# lsm_2x_daisy.net
KiCad netlist of a schematic drawn in EAGLE
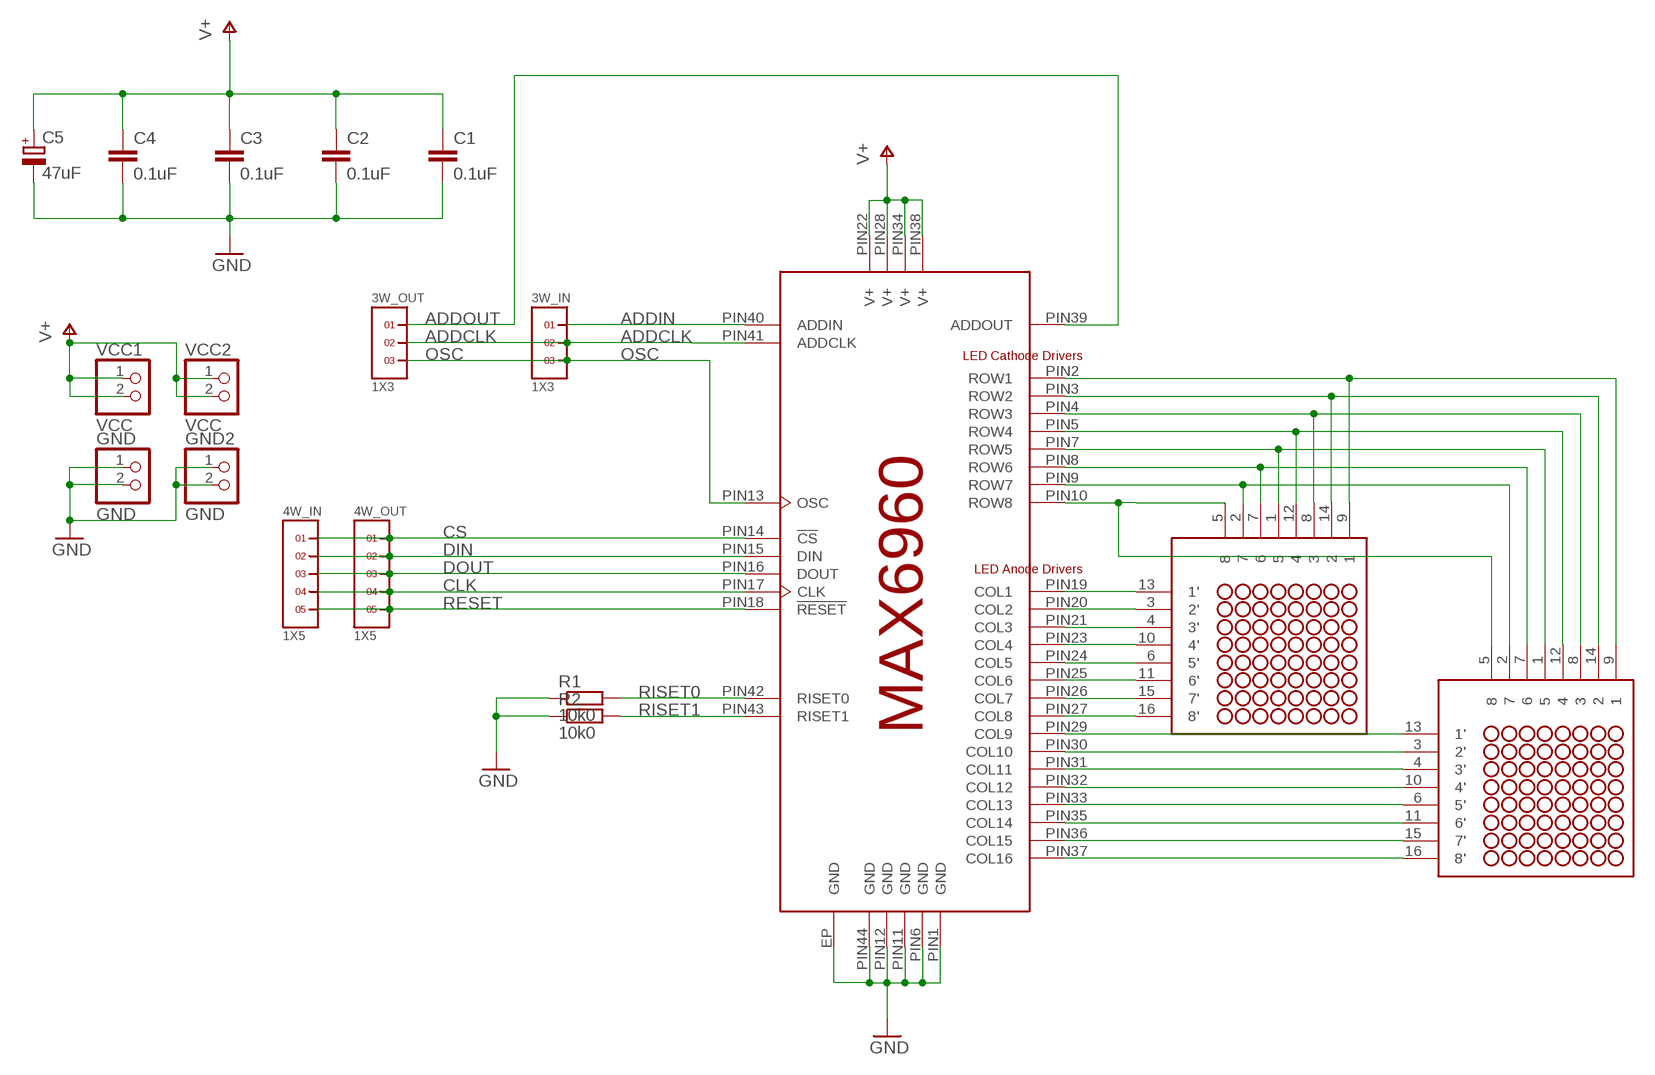
[diagram p0: schematic, sheet 1]

(export (version "E")
  (design (tool "Eeschema 10.0.6"))
  (components
    (comp (ref "3W_IN")
      (value "1X3")
      (footprint "eagle-import:1X3")
      (libsource (lib "eagle-import") (part "1X3"))
    )
    (comp (ref "3W_OUT")
      (value "1X3")
      (footprint "eagle-import:1X3")
      (libsource (lib "eagle-import") (part "1X3"))
    )
    (comp (ref "4W_IN")
      (value "1X5")
      (footprint "eagle-import:1X5")
      (libsource (lib "eagle-import") (part "1X5"))
    )
    (comp (ref "4W_OUT")
      (value "1X5")
      (footprint "eagle-import:1X5")
      (libsource (lib "eagle-import") (part "1X5"))
    )
    (comp (ref "C1")
      (value "0.1uF")
      (footprint "eagle-import:C0805")
      (libsource (lib "eagle-import") (part "C-EUC0805"))
    )
    (comp (ref "C2")
      (value "0.1uF")
      (footprint "eagle-import:C0805")
      (libsource (lib "eagle-import") (part "C-EUC0805"))
    )
    (comp (ref "C3")
      (value "0.1uF")
      (footprint "eagle-import:C0805")
      (libsource (lib "eagle-import") (part "C-EUC0805"))
    )
    (comp (ref "C4")
      (value "0.1uF")
      (footprint "eagle-import:C0805")
      (libsource (lib "eagle-import") (part "C-EUC0805"))
    )
    (comp (ref "C5")
      (value "47uF")
      (footprint "eagle-import:E2-5")
      (libsource (lib "eagle-import") (part "CPOL-EUE2-5"))
    )
    (comp (ref "GND")
      (value "GND")
      (footprint "eagle-import:1X02")
      (libsource (lib "eagle-import") (part "PINHD-1X2"))
    )
    (comp (ref "GND2")
      (value "GND")
      (footprint "eagle-import:1X02")
      (libsource (lib "eagle-import") (part "PINHD-1X2"))
    )
    (comp (ref "M1")
      (value "NFM-12881BG-11LILPADS")
      (footprint "eagle-import:NFM-12881BG-11-SMALL-LILPADS")
      (libsource (lib "eagle-import") (part "NFM-12881BG-11LILPADS"))
    )
    (comp (ref "M2")
      (value "NFM-12881BG-11LILPADS")
      (footprint "eagle-import:NFM-12881BG-11-SMALL-LILPADS")
      (libsource (lib "eagle-import") (part "NFM-12881BG-11LILPADS"))
    )
    (comp (ref "MAX6960")
      (value "MAX6960")
      (footprint "eagle-import:44TQFN-EP")
      (libsource (lib "eagle-import") (part "MAX6960"))
    )
    (comp (ref "R1")
      (value "10k0")
      (footprint "eagle-import:R0805")
      (libsource (lib "eagle-import") (part "R-EU_R0805"))
    )
    (comp (ref "R2")
      (value "10k0")
      (footprint "eagle-import:R0805")
      (libsource (lib "eagle-import") (part "R-EU_R0805"))
    )
    (comp (ref "VCC1")
      (value "VCC")
      (footprint "eagle-import:1X02")
      (libsource (lib "eagle-import") (part "PINHD-1X2"))
    )
    (comp (ref "VCC2")
      (value "VCC")
      (footprint "eagle-import:1X02")
      (libsource (lib "eagle-import") (part "PINHD-1X2"))
    )
  )
  (nets
    (net (code "1") (name "/ADDCLK") (class "Default")
      (node (ref "3W_IN") (pin "2") (pinfunction "2_2") (pintype "bidirectional"))
      (node (ref "3W_OUT") (pin "2") (pinfunction "2_2") (pintype "bidirectional"))
      (node (ref "MAX6960") (pin "PIN41") (pinfunction "ADDCLK_PIN41") (pintype "bidirectional"))
    )
    (net (code "2") (name "/ADDIN") (class "Default")
      (node (ref "3W_IN") (pin "1") (pinfunction "1_1") (pintype "bidirectional"))
      (node (ref "MAX6960") (pin "PIN40") (pinfunction "ADDIN_PIN40") (pintype "input"))
    )
    (net (code "3") (name "/ADDOUT") (class "Default")
      (node (ref "3W_OUT") (pin "1") (pinfunction "1_1") (pintype "bidirectional"))
      (node (ref "MAX6960") (pin "PIN39") (pinfunction "ADDOUT_PIN39") (pintype "output"))
    )
    (net (code "4") (name "/CLK") (class "Default")
      (node (ref "4W_IN") (pin "4") (pinfunction "4_4") (pintype "bidirectional"))
      (node (ref "4W_OUT") (pin "4") (pinfunction "4_4") (pintype "bidirectional"))
      (node (ref "MAX6960") (pin "PIN17") (pinfunction "CLK_PIN17") (pintype "input"))
    )
    (net (code "5") (name "/CS") (class "Default")
      (node (ref "4W_IN") (pin "1") (pinfunction "1_1") (pintype "bidirectional"))
      (node (ref "4W_OUT") (pin "1") (pinfunction "1_1") (pintype "bidirectional"))
      (node (ref "MAX6960") (pin "PIN14") (pinfunction "~{CS}_PIN14") (pintype "input"))
    )
    (net (code "6") (name "/DIN") (class "Default")
      (node (ref "4W_IN") (pin "2") (pinfunction "2_2") (pintype "bidirectional"))
      (node (ref "4W_OUT") (pin "2") (pinfunction "2_2") (pintype "bidirectional"))
      (node (ref "MAX6960") (pin "PIN15") (pinfunction "DIN_PIN15") (pintype "input"))
    )
    (net (code "7") (name "/DOUT") (class "Default")
      (node (ref "4W_IN") (pin "3") (pinfunction "3_3") (pintype "bidirectional"))
      (node (ref "4W_OUT") (pin "3") (pinfunction "3_3") (pintype "bidirectional"))
      (node (ref "MAX6960") (pin "PIN16") (pinfunction "DOUT_PIN16") (pintype "output"))
    )
    (net (code "8") (name "/OSC") (class "Default")
      (node (ref "3W_IN") (pin "3") (pinfunction "3_3") (pintype "bidirectional"))
      (node (ref "3W_OUT") (pin "3") (pinfunction "3_3") (pintype "bidirectional"))
      (node (ref "MAX6960") (pin "PIN13") (pinfunction "OSC_PIN13") (pintype "input"))
    )
    (net (code "9") (name "/RESET") (class "Default")
      (node (ref "4W_IN") (pin "5") (pinfunction "5_5") (pintype "bidirectional"))
      (node (ref "4W_OUT") (pin "5") (pinfunction "5_5") (pintype "bidirectional"))
      (node (ref "MAX6960") (pin "PIN18") (pinfunction "~{RESET}_PIN18") (pintype "input"))
    )
    (net (code "10") (name "/RISET0") (class "Default")
      (node (ref "MAX6960") (pin "PIN42") (pinfunction "RISET0_PIN42") (pintype "input"))
      (node (ref "R1") (pin "2") (pinfunction "2_2") (pintype "passive"))
    )
    (net (code "11") (name "/RISET1") (class "Default")
      (node (ref "MAX6960") (pin "PIN43") (pinfunction "RISET1_PIN43") (pintype "input"))
      (node (ref "R2") (pin "2") (pinfunction "2_2") (pintype "passive"))
    )
    (net (code "12") (name "GND") (class "Default")
      (node (ref "C1") (pin "2") (pinfunction "2_2") (pintype "passive"))
      (node (ref "C2") (pin "2") (pinfunction "2_2") (pintype "passive"))
      (node (ref "C3") (pin "2") (pinfunction "2_2") (pintype "passive"))
      (node (ref "C4") (pin "2") (pinfunction "2_2") (pintype "passive"))
      (node (ref "C5") (pin "-") (pinfunction "-_-") (pintype "passive"))
      (node (ref "GND") (pin "1") (pinfunction "1_1") (pintype "passive"))
      (node (ref "GND") (pin "2") (pinfunction "2_2") (pintype "passive"))
      (node (ref "GND2") (pin "1") (pinfunction "1_1") (pintype "passive"))
      (node (ref "GND2") (pin "2") (pinfunction "2_2") (pintype "passive"))
      (node (ref "MAX6960") (pin "EP") (pinfunction "GND_EP") (pintype "power_in"))
      (node (ref "MAX6960") (pin "PIN1") (pinfunction "GND_PIN1") (pintype "power_in"))
      (node (ref "MAX6960") (pin "PIN11") (pinfunction "GND_PIN11") (pintype "power_in"))
      (node (ref "MAX6960") (pin "PIN12") (pinfunction "GND_PIN12") (pintype "power_in"))
      (node (ref "MAX6960") (pin "PIN44") (pinfunction "GND_PIN44") (pintype "power_in"))
      (node (ref "MAX6960") (pin "PIN6") (pinfunction "GND_PIN6") (pintype "power_in"))
      (node (ref "R1") (pin "1") (pinfunction "1_1") (pintype "passive"))
      (node (ref "R2") (pin "1") (pinfunction "1_1") (pintype "passive"))
    )
    (net (code "13") (name "Net-(M1-1')") (class "Default")
      (node (ref "M1") (pin "13") (pinfunction "1'_13") (pintype "bidirectional"))
      (node (ref "MAX6960") (pin "PIN19") (pinfunction "COL1_PIN19") (pintype "output"))
    )
    (net (code "14") (name "Net-(M1-1)") (class "Default")
      (node (ref "M1") (pin "9") (pinfunction "1_9") (pintype "input"))
      (node (ref "M2") (pin "9") (pinfunction "1_9") (pintype "input"))
      (node (ref "MAX6960") (pin "PIN2") (pinfunction "ROW1_PIN2") (pintype "output"))
    )
    (net (code "15") (name "Net-(M1-2')") (class "Default")
      (node (ref "M1") (pin "3") (pinfunction "2'_3") (pintype "bidirectional"))
      (node (ref "MAX6960") (pin "PIN20") (pinfunction "COL2_PIN20") (pintype "output"))
    )
    (net (code "16") (name "Net-(M1-2)") (class "Default")
      (node (ref "M1") (pin "14") (pinfunction "2_14") (pintype "input"))
      (node (ref "M2") (pin "14") (pinfunction "2_14") (pintype "input"))
      (node (ref "MAX6960") (pin "PIN3") (pinfunction "ROW2_PIN3") (pintype "output"))
    )
    (net (code "17") (name "Net-(M1-3')") (class "Default")
      (node (ref "M1") (pin "4") (pinfunction "3'_4") (pintype "bidirectional"))
      (node (ref "MAX6960") (pin "PIN21") (pinfunction "COL3_PIN21") (pintype "output"))
    )
    (net (code "18") (name "Net-(M1-3)") (class "Default")
      (node (ref "M1") (pin "8") (pinfunction "3_8") (pintype "input"))
      (node (ref "M2") (pin "8") (pinfunction "3_8") (pintype "input"))
      (node (ref "MAX6960") (pin "PIN4") (pinfunction "ROW3_PIN4") (pintype "output"))
    )
    (net (code "19") (name "Net-(M1-4')") (class "Default")
      (node (ref "M1") (pin "10") (pinfunction "4'_10") (pintype "bidirectional"))
      (node (ref "MAX6960") (pin "PIN23") (pinfunction "COL4_PIN23") (pintype "output"))
    )
    (net (code "20") (name "Net-(M1-4)") (class "Default")
      (node (ref "M1") (pin "12") (pinfunction "4_12") (pintype "input"))
      (node (ref "M2") (pin "12") (pinfunction "4_12") (pintype "input"))
      (node (ref "MAX6960") (pin "PIN5") (pinfunction "ROW4_PIN5") (pintype "output"))
    )
    (net (code "21") (name "Net-(M1-5')") (class "Default")
      (node (ref "M1") (pin "6") (pinfunction "5'_6") (pintype "bidirectional"))
      (node (ref "MAX6960") (pin "PIN24") (pinfunction "COL5_PIN24") (pintype "output"))
    )
    (net (code "22") (name "Net-(M1-5)") (class "Default")
      (node (ref "M1") (pin "1") (pinfunction "5_1") (pintype "input"))
      (node (ref "M2") (pin "1") (pinfunction "5_1") (pintype "input"))
      (node (ref "MAX6960") (pin "PIN7") (pinfunction "ROW5_PIN7") (pintype "output"))
    )
    (net (code "23") (name "Net-(M1-6')") (class "Default")
      (node (ref "M1") (pin "11") (pinfunction "6'_11") (pintype "bidirectional"))
      (node (ref "MAX6960") (pin "PIN25") (pinfunction "COL6_PIN25") (pintype "output"))
    )
    (net (code "24") (name "Net-(M1-6)") (class "Default")
      (node (ref "M1") (pin "7") (pinfunction "6_7") (pintype "input"))
      (node (ref "M2") (pin "7") (pinfunction "6_7") (pintype "input"))
      (node (ref "MAX6960") (pin "PIN8") (pinfunction "ROW6_PIN8") (pintype "output"))
    )
    (net (code "25") (name "Net-(M1-7')") (class "Default")
      (node (ref "M1") (pin "15") (pinfunction "7'_15") (pintype "bidirectional"))
      (node (ref "MAX6960") (pin "PIN26") (pinfunction "COL7_PIN26") (pintype "output"))
    )
    (net (code "26") (name "Net-(M1-7)") (class "Default")
      (node (ref "M1") (pin "2") (pinfunction "7_2") (pintype "input"))
      (node (ref "M2") (pin "2") (pinfunction "7_2") (pintype "input"))
      (node (ref "MAX6960") (pin "PIN9") (pinfunction "ROW7_PIN9") (pintype "output"))
    )
    (net (code "27") (name "Net-(M1-8')") (class "Default")
      (node (ref "M1") (pin "16") (pinfunction "8'_16") (pintype "bidirectional"))
      (node (ref "MAX6960") (pin "PIN27") (pinfunction "COL8_PIN27") (pintype "output"))
    )
    (net (code "28") (name "Net-(M1-8)") (class "Default")
      (node (ref "M1") (pin "5") (pinfunction "8_5") (pintype "input"))
      (node (ref "M2") (pin "5") (pinfunction "8_5") (pintype "input"))
      (node (ref "MAX6960") (pin "PIN10") (pinfunction "ROW8_PIN10") (pintype "output"))
    )
    (net (code "29") (name "Net-(M2-1')") (class "Default")
      (node (ref "M2") (pin "13") (pinfunction "1'_13") (pintype "bidirectional"))
      (node (ref "MAX6960") (pin "PIN29") (pinfunction "COL9_PIN29") (pintype "output"))
    )
    (net (code "30") (name "Net-(M2-2')") (class "Default")
      (node (ref "M2") (pin "3") (pinfunction "2'_3") (pintype "bidirectional"))
      (node (ref "MAX6960") (pin "PIN30") (pinfunction "COL10_PIN30") (pintype "output"))
    )
    (net (code "31") (name "Net-(M2-3')") (class "Default")
      (node (ref "M2") (pin "4") (pinfunction "3'_4") (pintype "bidirectional"))
      (node (ref "MAX6960") (pin "PIN31") (pinfunction "COL11_PIN31") (pintype "output"))
    )
    (net (code "32") (name "Net-(M2-4')") (class "Default")
      (node (ref "M2") (pin "10") (pinfunction "4'_10") (pintype "bidirectional"))
      (node (ref "MAX6960") (pin "PIN32") (pinfunction "COL12_PIN32") (pintype "output"))
    )
    (net (code "33") (name "Net-(M2-5')") (class "Default")
      (node (ref "M2") (pin "6") (pinfunction "5'_6") (pintype "bidirectional"))
      (node (ref "MAX6960") (pin "PIN33") (pinfunction "COL13_PIN33") (pintype "output"))
    )
    (net (code "34") (name "Net-(M2-6')") (class "Default")
      (node (ref "M2") (pin "11") (pinfunction "6'_11") (pintype "bidirectional"))
      (node (ref "MAX6960") (pin "PIN35") (pinfunction "COL14_PIN35") (pintype "output"))
    )
    (net (code "35") (name "Net-(M2-7')") (class "Default")
      (node (ref "M2") (pin "15") (pinfunction "7'_15") (pintype "bidirectional"))
      (node (ref "MAX6960") (pin "PIN36") (pinfunction "COL15_PIN36") (pintype "output"))
    )
    (net (code "36") (name "Net-(M2-8')") (class "Default")
      (node (ref "M2") (pin "16") (pinfunction "8'_16") (pintype "bidirectional"))
      (node (ref "MAX6960") (pin "PIN37") (pinfunction "COL16_PIN37") (pintype "output"))
    )
    (net (code "37") (name "V+") (class "Default")
      (node (ref "C1") (pin "1") (pinfunction "1_1") (pintype "passive"))
      (node (ref "C2") (pin "1") (pinfunction "1_1") (pintype "passive"))
      (node (ref "C3") (pin "1") (pinfunction "1_1") (pintype "passive"))
      (node (ref "C4") (pin "1") (pinfunction "1_1") (pintype "passive"))
      (node (ref "C5") (pin "+") (pinfunction "+_+") (pintype "passive"))
      (node (ref "MAX6960") (pin "PIN22") (pinfunction "V+_PIN22") (pintype "power_in"))
      (node (ref "MAX6960") (pin "PIN28") (pinfunction "V+_PIN28") (pintype "power_in"))
      (node (ref "MAX6960") (pin "PIN34") (pinfunction "V+_PIN34") (pintype "power_in"))
      (node (ref "MAX6960") (pin "PIN38") (pinfunction "V+_PIN38") (pintype "power_in"))
      (node (ref "VCC1") (pin "1") (pinfunction "1_1") (pintype "passive"))
      (node (ref "VCC1") (pin "2") (pinfunction "2_2") (pintype "passive"))
      (node (ref "VCC2") (pin "1") (pinfunction "1_1") (pintype "passive"))
      (node (ref "VCC2") (pin "2") (pinfunction "2_2") (pintype "passive"))
    )
  )
)
